# featherwing-interface.net
KiCad netlist of a schematic drawn in EAGLE
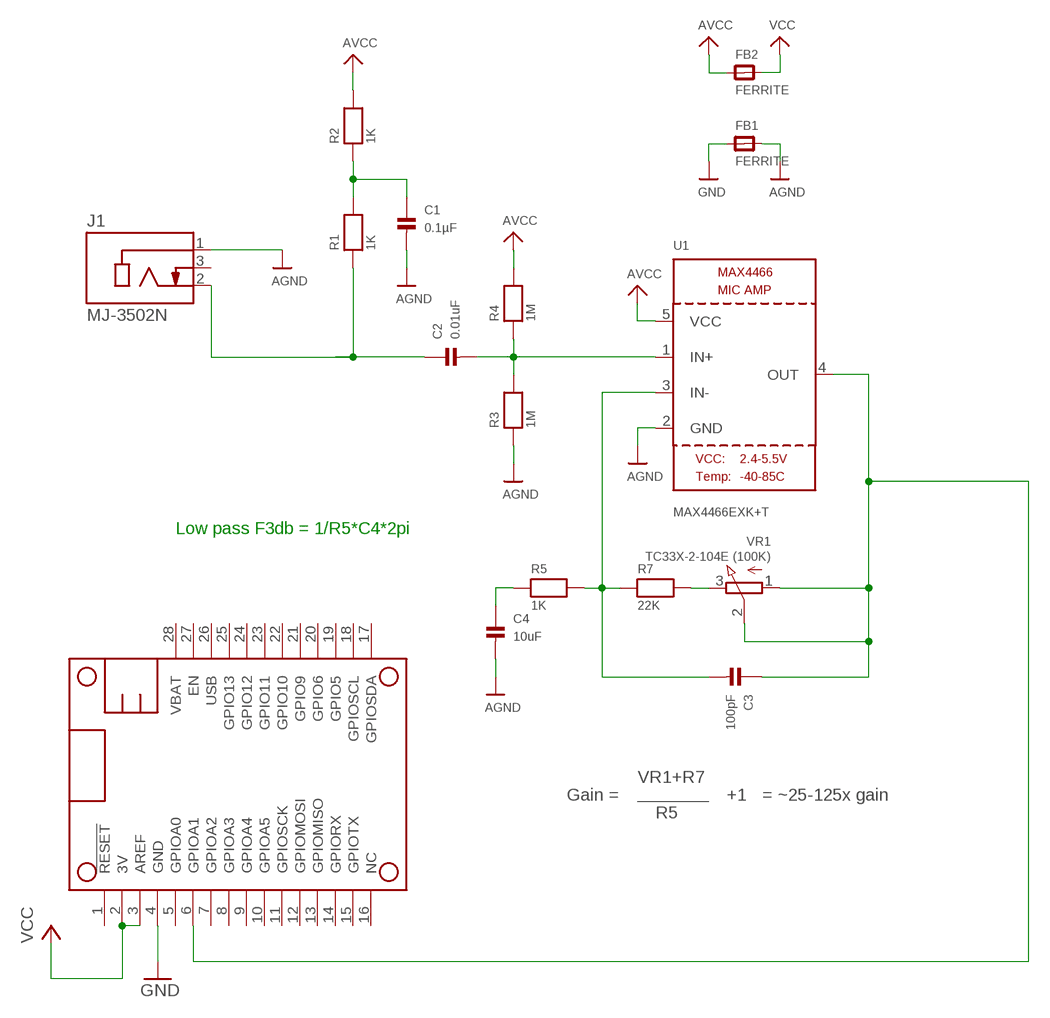
[diagram p0: schematic, sheet 1]

(export (version "E")
  (design (tool "Eeschema 10.0.6"))
  (components
    (comp (ref "C1")
      (value "0.1µF")
      (footprint "eagle-import:0805")
      (libsource (lib "eagle-import") (part "CAP_CERAMIC0805"))
    )
    (comp (ref "C2")
      (value "0.01uF")
      (footprint "eagle-import:0805")
      (libsource (lib "eagle-import") (part "CAP_CERAMIC0805"))
    )
    (comp (ref "C3")
      (value "100pF")
      (footprint "eagle-import:0805")
      (libsource (lib "eagle-import") (part "CAP_CERAMIC0805"))
    )
    (comp (ref "C4")
      (value "10uF")
      (footprint "eagle-import:0805")
      (libsource (lib "eagle-import") (part "CAP_CERAMIC0805"))
    )
    (comp (ref "FB1")
      (value "FERRITE")
      (footprint "eagle-import:0805")
      (libsource (lib "eagle-import") (part "FERRITE0805"))
    )
    (comp (ref "FB2")
      (value "FERRITE")
      (footprint "eagle-import:0805")
      (libsource (lib "eagle-import") (part "FERRITE0805"))
    )
    (comp (ref "J1")
      (value "MJ-3502N")
      (footprint "eagle-import:CUI_MJ-3502N")
      (fields (field (name "MANUFACTURER") "CUI INC"))
      (libsource (lib "eagle-import") (part "MJ-3502N"))
    )
    (comp (ref "MS1")
      (value "FEATHERWING")
      (footprint "eagle-import:FEATHERWING")
      (libsource (lib "eagle-import") (part "FEATHERWING"))
    )
    (comp (ref "R1")
      (value "1K")
      (footprint "eagle-import:0805")
      (libsource (lib "eagle-import") (part "RESISTOR0805"))
    )
    (comp (ref "R2")
      (value "1K")
      (footprint "eagle-import:0805")
      (libsource (lib "eagle-import") (part "RESISTOR0805"))
    )
    (comp (ref "R3")
      (value "1M")
      (footprint "eagle-import:0805")
      (libsource (lib "eagle-import") (part "RESISTOR0805"))
    )
    (comp (ref "R4")
      (value "1M")
      (footprint "eagle-import:0805")
      (libsource (lib "eagle-import") (part "RESISTOR0805"))
    )
    (comp (ref "R5")
      (value "1K")
      (footprint "eagle-import:0805")
      (libsource (lib "eagle-import") (part "RESISTOR0805"))
    )
    (comp (ref "R7")
      (value "22K")
      (footprint "eagle-import:0805")
      (libsource (lib "eagle-import") (part "RESISTOR0805"))
    )
    (comp (ref "U1")
      (value "MAX4466EXK+T")
      (footprint "eagle-import:SC70-5")
      (libsource (lib "eagle-import") (part "MAX4466{dblquote}{dblquote}"))
    )
    (comp (ref "VR1")
      (value "TC33X-2-104E (100K)")
      (footprint "eagle-import:TRIMPOT_BOURNS_TC33X-2")
      (libsource (lib "eagle-import") (part "TRIMPOTTC33X-2"))
    )
  )
  (nets
    (net (code "1") (name "/USB") (class "Default")
      (node (ref "MS1") (pin "26") (pinfunction "USB_26") (pintype "power_in"))
    )
    (net (code "2") (name "/VBAT") (class "Default")
      (node (ref "MS1") (pin "28") (pinfunction "VBAT_28") (pintype "power_in"))
    )
    (net (code "3") (name "AGND") (class "Default")
      (node (ref "C1") (pin "2") (pinfunction "P$2_2") (pintype "passive"))
      (node (ref "C4") (pin "2") (pinfunction "P$2_2") (pintype "passive"))
      (node (ref "FB1") (pin "2") (pinfunction "P$2_2") (pintype "passive"))
      (node (ref "J1") (pin "1") (pinfunction "1_1") (pintype "passive"))
      (node (ref "R3") (pin "1") (pinfunction "1_1") (pintype "passive"))
      (node (ref "U1") (pin "2") (pinfunction "GND_2") (pintype "bidirectional"))
    )
    (net (code "4") (name "AVCC") (class "Default")
      (node (ref "FB2") (pin "1") (pinfunction "P$1_1") (pintype "passive"))
      (node (ref "R2") (pin "2") (pinfunction "2_2") (pintype "passive"))
      (node (ref "R4") (pin "2") (pinfunction "2_2") (pintype "passive"))
      (node (ref "U1") (pin "5") (pinfunction "VCC_5") (pintype "bidirectional"))
    )
    (net (code "5") (name "GND") (class "Default")
      (node (ref "FB1") (pin "1") (pinfunction "P$1_1") (pintype "passive"))
      (node (ref "MS1") (pin "4") (pinfunction "GND_4") (pintype "power_in"))
    )
    (net (code "6") (name "Net-(C1-P$1)") (class "Default")
      (node (ref "C1") (pin "1") (pinfunction "P$1_1") (pintype "passive"))
      (node (ref "R1") (pin "2") (pinfunction "2_2") (pintype "passive"))
      (node (ref "R2") (pin "1") (pinfunction "1_1") (pintype "passive"))
    )
    (net (code "7") (name "Net-(C2-P$1)") (class "Default")
      (node (ref "C2") (pin "1") (pinfunction "P$1_1") (pintype "passive"))
      (node (ref "J1") (pin "2") (pinfunction "2_2") (pintype "passive"))
      (node (ref "R1") (pin "1") (pinfunction "1_1") (pintype "passive"))
    )
    (net (code "8") (name "Net-(C2-P$2)") (class "Default")
      (node (ref "C2") (pin "2") (pinfunction "P$2_2") (pintype "passive"))
      (node (ref "R3") (pin "2") (pinfunction "2_2") (pintype "passive"))
      (node (ref "R4") (pin "1") (pinfunction "1_1") (pintype "passive"))
      (node (ref "U1") (pin "1") (pinfunction "IN+_1") (pintype "bidirectional"))
    )
    (net (code "9") (name "Net-(C3-P$1)") (class "Default")
      (node (ref "C3") (pin "1") (pinfunction "P$1_1") (pintype "passive"))
      (node (ref "MS1") (pin "6") (pinfunction "GPIOA1_6") (pintype "bidirectional"))
      (node (ref "U1") (pin "4") (pinfunction "OUT_4") (pintype "bidirectional"))
      (node (ref "VR1") (pin "1") (pinfunction "A_1") (pintype "passive"))
      (node (ref "VR1") (pin "2") (pinfunction "S_2") (pintype "passive"))
    )
    (net (code "10") (name "Net-(C3-P$2)") (class "Default")
      (node (ref "C3") (pin "2") (pinfunction "P$2_2") (pintype "passive"))
      (node (ref "R5") (pin "2") (pinfunction "2_2") (pintype "passive"))
      (node (ref "R7") (pin "1") (pinfunction "1_1") (pintype "passive"))
      (node (ref "U1") (pin "3") (pinfunction "IN-_3") (pintype "bidirectional"))
    )
    (net (code "11") (name "Net-(C4-P$1)") (class "Default")
      (node (ref "C4") (pin "1") (pinfunction "P$1_1") (pintype "passive"))
      (node (ref "R5") (pin "1") (pinfunction "1_1") (pintype "passive"))
    )
    (net (code "12") (name "Net-(VR1-E)") (class "Default")
      (node (ref "R7") (pin "2") (pinfunction "2_2") (pintype "passive"))
      (node (ref "VR1") (pin "3") (pinfunction "E_3") (pintype "passive"))
    )
    (net (code "13") (name "VCC") (class "Default")
      (node (ref "FB2") (pin "2") (pinfunction "P$2_2") (pintype "passive"))
      (node (ref "MS1") (pin "2") (pinfunction "3V_2") (pintype "power_in"))
      (node (ref "MS1") (pin "3") (pinfunction "AREF_3") (pintype "passive"))
    )
    (net (code "14") (name "unconnected-(J1-Pad3)") (class "Default")
      (node (ref "J1") (pin "3") (pinfunction "3_3") (pintype "passive"))
    )
    (net (code "15") (name "unconnected-(MS1-EN-Pad27)") (class "Default")
      (node (ref "MS1") (pin "27") (pinfunction "EN_27") (pintype "passive"))
    )
    (net (code "16") (name "unconnected-(MS1-GPIO5-Pad19)") (class "Default")
      (node (ref "MS1") (pin "19") (pinfunction "GPIO5_19") (pintype "bidirectional"))
    )
    (net (code "17") (name "unconnected-(MS1-GPIO6-Pad20)") (class "Default")
      (node (ref "MS1") (pin "20") (pinfunction "GPIO6_20") (pintype "bidirectional"))
    )
    (net (code "18") (name "unconnected-(MS1-GPIO9-Pad21)") (class "Default")
      (node (ref "MS1") (pin "21") (pinfunction "GPIO9_21") (pintype "bidirectional"))
    )
    (net (code "19") (name "unconnected-(MS1-GPIO10-Pad22)") (class "Default")
      (node (ref "MS1") (pin "22") (pinfunction "GPIO10_22") (pintype "bidirectional"))
    )
    (net (code "20") (name "unconnected-(MS1-GPIO11-Pad23)") (class "Default")
      (node (ref "MS1") (pin "23") (pinfunction "GPIO11_23") (pintype "bidirectional"))
    )
    (net (code "21") (name "unconnected-(MS1-GPIO12-Pad24)") (class "Default")
      (node (ref "MS1") (pin "24") (pinfunction "GPIO12_24") (pintype "bidirectional"))
    )
    (net (code "22") (name "unconnected-(MS1-GPIO13-Pad25)") (class "Default")
      (node (ref "MS1") (pin "25") (pinfunction "GPIO13_25") (pintype "bidirectional"))
    )
    (net (code "23") (name "unconnected-(MS1-GPIOA0-Pad5)") (class "Default")
      (node (ref "MS1") (pin "5") (pinfunction "GPIOA0_5") (pintype "bidirectional"))
    )
    (net (code "24") (name "unconnected-(MS1-GPIOA2-Pad7)") (class "Default")
      (node (ref "MS1") (pin "7") (pinfunction "GPIOA2_7") (pintype "bidirectional"))
    )
    (net (code "25") (name "unconnected-(MS1-GPIOA3-Pad8)") (class "Default")
      (node (ref "MS1") (pin "8") (pinfunction "GPIOA3_8") (pintype "bidirectional"))
    )
    (net (code "26") (name "unconnected-(MS1-GPIOA4-Pad9)") (class "Default")
      (node (ref "MS1") (pin "9") (pinfunction "GPIOA4_9") (pintype "bidirectional"))
    )
    (net (code "27") (name "unconnected-(MS1-GPIOA5-Pad10)") (class "Default")
      (node (ref "MS1") (pin "10") (pinfunction "GPIOA5_10") (pintype "bidirectional"))
    )
    (net (code "28") (name "unconnected-(MS1-GPIOMISO-Pad13)") (class "Default")
      (node (ref "MS1") (pin "13") (pinfunction "GPIOMISO_13") (pintype "bidirectional"))
    )
    (net (code "29") (name "unconnected-(MS1-GPIOMOSI-Pad12)") (class "Default")
      (node (ref "MS1") (pin "12") (pinfunction "GPIOMOSI_12") (pintype "bidirectional"))
    )
    (net (code "30") (name "unconnected-(MS1-GPIORX-Pad14)") (class "Default")
      (node (ref "MS1") (pin "14") (pinfunction "GPIORX_14") (pintype "bidirectional"))
    )
    (net (code "31") (name "unconnected-(MS1-GPIOSCK-Pad11)") (class "Default")
      (node (ref "MS1") (pin "11") (pinfunction "GPIOSCK_11") (pintype "bidirectional"))
    )
    (net (code "32") (name "unconnected-(MS1-GPIOSCL-Pad18)") (class "Default")
      (node (ref "MS1") (pin "18") (pinfunction "GPIOSCL_18") (pintype "bidirectional"))
    )
    (net (code "33") (name "unconnected-(MS1-GPIOSDA-Pad17)") (class "Default")
      (node (ref "MS1") (pin "17") (pinfunction "GPIOSDA_17") (pintype "bidirectional"))
    )
    (net (code "34") (name "unconnected-(MS1-GPIOTX-Pad15)") (class "Default")
      (node (ref "MS1") (pin "15") (pinfunction "GPIOTX_15") (pintype "bidirectional"))
    )
    (net (code "35") (name "unconnected-(MS1-NC-Pad16)") (class "Default")
      (node (ref "MS1") (pin "16") (pinfunction "NC_16") (pintype "passive"))
    )
    (net (code "36") (name "unconnected-(MS1-~{RESET}-Pad1)") (class "Default")
      (node (ref "MS1") (pin "1") (pinfunction "~{RESET}_1") (pintype "input"))
    )
  )
)
